# RowDriver2.net
KiCad netlist of a schematic drawn in EAGLE
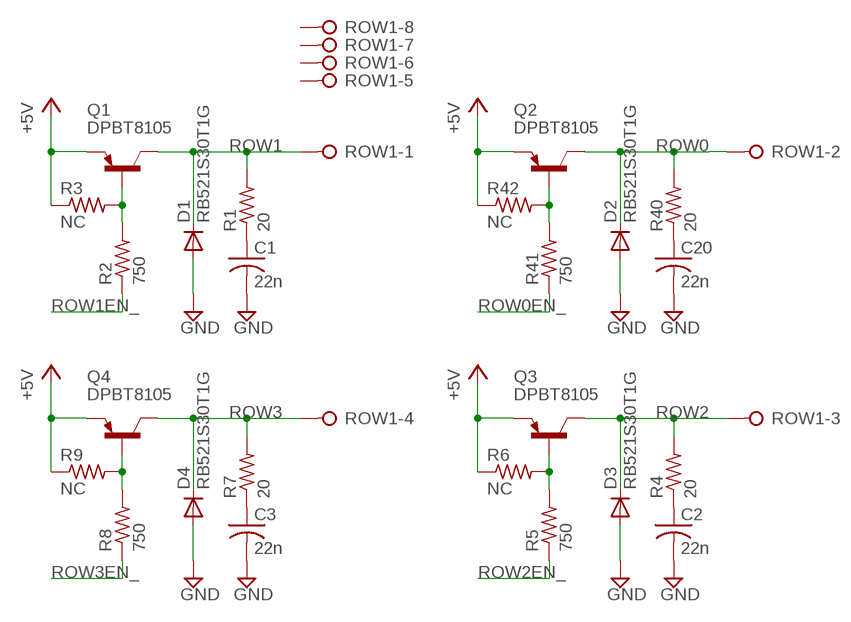
[diagram p0: schematic, sheet 1]

(export (version "E")
  (design (tool "Eeschema 10.0.6"))
  (components
    (comp (ref "C1")
      (value "22n")
      (footprint "eagle-import:C0603")
      (libsource (lib "eagle-import") (part "C-USC0603"))
    )
    (comp (ref "C2")
      (value "22n")
      (footprint "eagle-import:C0603")
      (libsource (lib "eagle-import") (part "C-USC0603"))
    )
    (comp (ref "C3")
      (value "22n")
      (footprint "eagle-import:C0603")
      (libsource (lib "eagle-import") (part "C-USC0603"))
    )
    (comp (ref "C20")
      (value "22n")
      (footprint "eagle-import:C0603")
      (libsource (lib "eagle-import") (part "C-USC0603"))
    )
    (comp (ref "D1")
      (value "RB521S30T1G")
      (footprint "eagle-import:SOD523")
      (libsource (lib "eagle-import") (part "DIODE-SOD523"))
    )
    (comp (ref "D2")
      (value "RB521S30T1G")
      (footprint "eagle-import:SOD523")
      (libsource (lib "eagle-import") (part "DIODE-SOD523"))
    )
    (comp (ref "D3")
      (value "RB521S30T1G")
      (footprint "eagle-import:SOD523")
      (libsource (lib "eagle-import") (part "DIODE-SOD523"))
    )
    (comp (ref "D4")
      (value "RB521S30T1G")
      (footprint "eagle-import:SOD523")
      (libsource (lib "eagle-import") (part "DIODE-SOD523"))
    )
    (comp (ref "Q1")
      (value "DPBT8105")
      (footprint "eagle-import:SOT23")
      (libsource (lib "eagle-import") (part "DPBT8105"))
    )
    (comp (ref "Q2")
      (value "DPBT8105")
      (footprint "eagle-import:SOT23")
      (libsource (lib "eagle-import") (part "DPBT8105"))
    )
    (comp (ref "Q3")
      (value "DPBT8105")
      (footprint "eagle-import:SOT23")
      (libsource (lib "eagle-import") (part "DPBT8105"))
    )
    (comp (ref "Q4")
      (value "DPBT8105")
      (footprint "eagle-import:SOT23")
      (libsource (lib "eagle-import") (part "DPBT8105"))
    )
    (comp (ref "R1")
      (value "20")
      (footprint "eagle-import:R0603")
      (libsource (lib "eagle-import") (part "R-US_R0603"))
    )
    (comp (ref "R2")
      (value "750")
      (footprint "eagle-import:R0603")
      (libsource (lib "eagle-import") (part "R-US_R0603"))
    )
    (comp (ref "R3")
      (value "NC")
      (footprint "eagle-import:R0603")
      (libsource (lib "eagle-import") (part "R-US_R0603"))
    )
    (comp (ref "R4")
      (value "20")
      (footprint "eagle-import:R0603")
      (libsource (lib "eagle-import") (part "R-US_R0603"))
    )
    (comp (ref "R5")
      (value "750")
      (footprint "eagle-import:R0603")
      (libsource (lib "eagle-import") (part "R-US_R0603"))
    )
    (comp (ref "R6")
      (value "NC")
      (footprint "eagle-import:R0603")
      (libsource (lib "eagle-import") (part "R-US_R0603"))
    )
    (comp (ref "R7")
      (value "20")
      (footprint "eagle-import:R0603")
      (libsource (lib "eagle-import") (part "R-US_R0603"))
    )
    (comp (ref "R8")
      (value "750")
      (footprint "eagle-import:R0603")
      (libsource (lib "eagle-import") (part "R-US_R0603"))
    )
    (comp (ref "R9")
      (value "NC")
      (footprint "eagle-import:R0603")
      (libsource (lib "eagle-import") (part "R-US_R0603"))
    )
    (comp (ref "R40")
      (value "20")
      (footprint "eagle-import:R0603")
      (libsource (lib "eagle-import") (part "R-US_R0603"))
    )
    (comp (ref "R41")
      (value "750")
      (footprint "eagle-import:R0603")
      (libsource (lib "eagle-import") (part "R-US_R0603"))
    )
    (comp (ref "R42")
      (value "NC")
      (footprint "eagle-import:R0603")
      (libsource (lib "eagle-import") (part "R-US_R0603"))
    )
    (comp (ref "ROW1")
      (value "OSTVN08A150")
      (footprint "eagle-import:OSTVN08")
      (libsource (lib "eagle-import") (part "OSTVN08A150"))
    )
  )
  (nets
    (net (code "1") (name "+5V") (class "Default")
      (node (ref "Q1") (pin "2") (pinfunction "E_2") (pintype "passive"))
      (node (ref "Q2") (pin "2") (pinfunction "E_2") (pintype "passive"))
      (node (ref "Q3") (pin "2") (pinfunction "E_2") (pintype "passive"))
      (node (ref "Q4") (pin "2") (pinfunction "E_2") (pintype "passive"))
      (node (ref "R3") (pin "1") (pinfunction "1_1") (pintype "passive"))
      (node (ref "R42") (pin "1") (pinfunction "1_1") (pintype "passive"))
      (node (ref "R6") (pin "1") (pinfunction "1_1") (pintype "passive"))
      (node (ref "R9") (pin "1") (pinfunction "1_1") (pintype "passive"))
    )
    (net (code "2") (name "/ROW0") (class "Default")
      (node (ref "D2") (pin "C") (pinfunction "C_C") (pintype "passive"))
      (node (ref "Q2") (pin "3") (pinfunction "C_3") (pintype "passive"))
      (node (ref "R40") (pin "2") (pinfunction "2_2") (pintype "passive"))
      (node (ref "ROW1") (pin "2") (pinfunction "KL_2") (pintype "passive"))
    )
    (net (code "3") (name "/ROW0EN_") (class "Default")
      (node (ref "R41") (pin "1") (pinfunction "1_1") (pintype "passive"))
    )
    (net (code "4") (name "/ROW1") (class "Default")
      (node (ref "D1") (pin "C") (pinfunction "C_C") (pintype "passive"))
      (node (ref "Q1") (pin "3") (pinfunction "C_3") (pintype "passive"))
      (node (ref "R1") (pin "2") (pinfunction "2_2") (pintype "passive"))
      (node (ref "ROW1") (pin "1") (pinfunction "KL_1") (pintype "passive"))
    )
    (net (code "5") (name "/ROW1EN_") (class "Default")
      (node (ref "R2") (pin "1") (pinfunction "1_1") (pintype "passive"))
    )
    (net (code "6") (name "/ROW2") (class "Default")
      (node (ref "D3") (pin "C") (pinfunction "C_C") (pintype "passive"))
      (node (ref "Q3") (pin "3") (pinfunction "C_3") (pintype "passive"))
      (node (ref "R4") (pin "2") (pinfunction "2_2") (pintype "passive"))
      (node (ref "ROW1") (pin "3") (pinfunction "KL_3") (pintype "passive"))
    )
    (net (code "7") (name "/ROW2EN_") (class "Default")
      (node (ref "R5") (pin "1") (pinfunction "1_1") (pintype "passive"))
    )
    (net (code "8") (name "/ROW3") (class "Default")
      (node (ref "D4") (pin "C") (pinfunction "C_C") (pintype "passive"))
      (node (ref "Q4") (pin "3") (pinfunction "C_3") (pintype "passive"))
      (node (ref "R7") (pin "2") (pinfunction "2_2") (pintype "passive"))
      (node (ref "ROW1") (pin "4") (pinfunction "KL_4") (pintype "passive"))
    )
    (net (code "9") (name "/ROW3EN_") (class "Default")
      (node (ref "R8") (pin "1") (pinfunction "1_1") (pintype "passive"))
    )
    (net (code "10") (name "GND") (class "Default")
      (node (ref "C1") (pin "2") (pinfunction "2_2") (pintype "passive"))
      (node (ref "C2") (pin "2") (pinfunction "2_2") (pintype "passive"))
      (node (ref "C20") (pin "2") (pinfunction "2_2") (pintype "passive"))
      (node (ref "C3") (pin "2") (pinfunction "2_2") (pintype "passive"))
      (node (ref "D1") (pin "A") (pinfunction "A_A") (pintype "passive"))
      (node (ref "D2") (pin "A") (pinfunction "A_A") (pintype "passive"))
      (node (ref "D3") (pin "A") (pinfunction "A_A") (pintype "passive"))
      (node (ref "D4") (pin "A") (pinfunction "A_A") (pintype "passive"))
    )
    (net (code "11") (name "Net-(C1-Pad1)") (class "Default")
      (node (ref "C1") (pin "1") (pinfunction "1_1") (pintype "passive"))
      (node (ref "R1") (pin "1") (pinfunction "1_1") (pintype "passive"))
    )
    (net (code "12") (name "Net-(C2-Pad1)") (class "Default")
      (node (ref "C2") (pin "1") (pinfunction "1_1") (pintype "passive"))
      (node (ref "R4") (pin "1") (pinfunction "1_1") (pintype "passive"))
    )
    (net (code "13") (name "Net-(C3-Pad1)") (class "Default")
      (node (ref "C3") (pin "1") (pinfunction "1_1") (pintype "passive"))
      (node (ref "R7") (pin "1") (pinfunction "1_1") (pintype "passive"))
    )
    (net (code "14") (name "Net-(C20-Pad1)") (class "Default")
      (node (ref "C20") (pin "1") (pinfunction "1_1") (pintype "passive"))
      (node (ref "R40") (pin "1") (pinfunction "1_1") (pintype "passive"))
    )
    (net (code "15") (name "Net-(Q1-B)") (class "Default")
      (node (ref "Q1") (pin "1") (pinfunction "B_1") (pintype "passive"))
      (node (ref "R2") (pin "2") (pinfunction "2_2") (pintype "passive"))
      (node (ref "R3") (pin "2") (pinfunction "2_2") (pintype "passive"))
    )
    (net (code "16") (name "Net-(Q2-B)") (class "Default")
      (node (ref "Q2") (pin "1") (pinfunction "B_1") (pintype "passive"))
      (node (ref "R41") (pin "2") (pinfunction "2_2") (pintype "passive"))
      (node (ref "R42") (pin "2") (pinfunction "2_2") (pintype "passive"))
    )
    (net (code "17") (name "Net-(Q3-B)") (class "Default")
      (node (ref "Q3") (pin "1") (pinfunction "B_1") (pintype "passive"))
      (node (ref "R5") (pin "2") (pinfunction "2_2") (pintype "passive"))
      (node (ref "R6") (pin "2") (pinfunction "2_2") (pintype "passive"))
    )
    (net (code "18") (name "Net-(Q4-B)") (class "Default")
      (node (ref "Q4") (pin "1") (pinfunction "B_1") (pintype "passive"))
      (node (ref "R8") (pin "2") (pinfunction "2_2") (pintype "passive"))
      (node (ref "R9") (pin "2") (pinfunction "2_2") (pintype "passive"))
    )
    (net (code "19") (name "unconnected-(ROW1E-KL-Pad5)") (class "Default")
      (node (ref "ROW1") (pin "5") (pinfunction "KL_5") (pintype "passive"))
    )
    (net (code "20") (name "unconnected-(ROW1F-KL-Pad6)") (class "Default")
      (node (ref "ROW1") (pin "6") (pinfunction "KL_6") (pintype "passive"))
    )
    (net (code "21") (name "unconnected-(ROW1G-KL-Pad7)") (class "Default")
      (node (ref "ROW1") (pin "7") (pinfunction "KL_7") (pintype "passive"))
    )
    (net (code "22") (name "unconnected-(ROW1H-KL-Pad8)") (class "Default")
      (node (ref "ROW1") (pin "8") (pinfunction "KL_8") (pintype "passive"))
    )
  )
)
